# SCH_IoT_STANDALONE_2024-02-11.net
KiCad netlist of a schematic drawn in EasyEDA
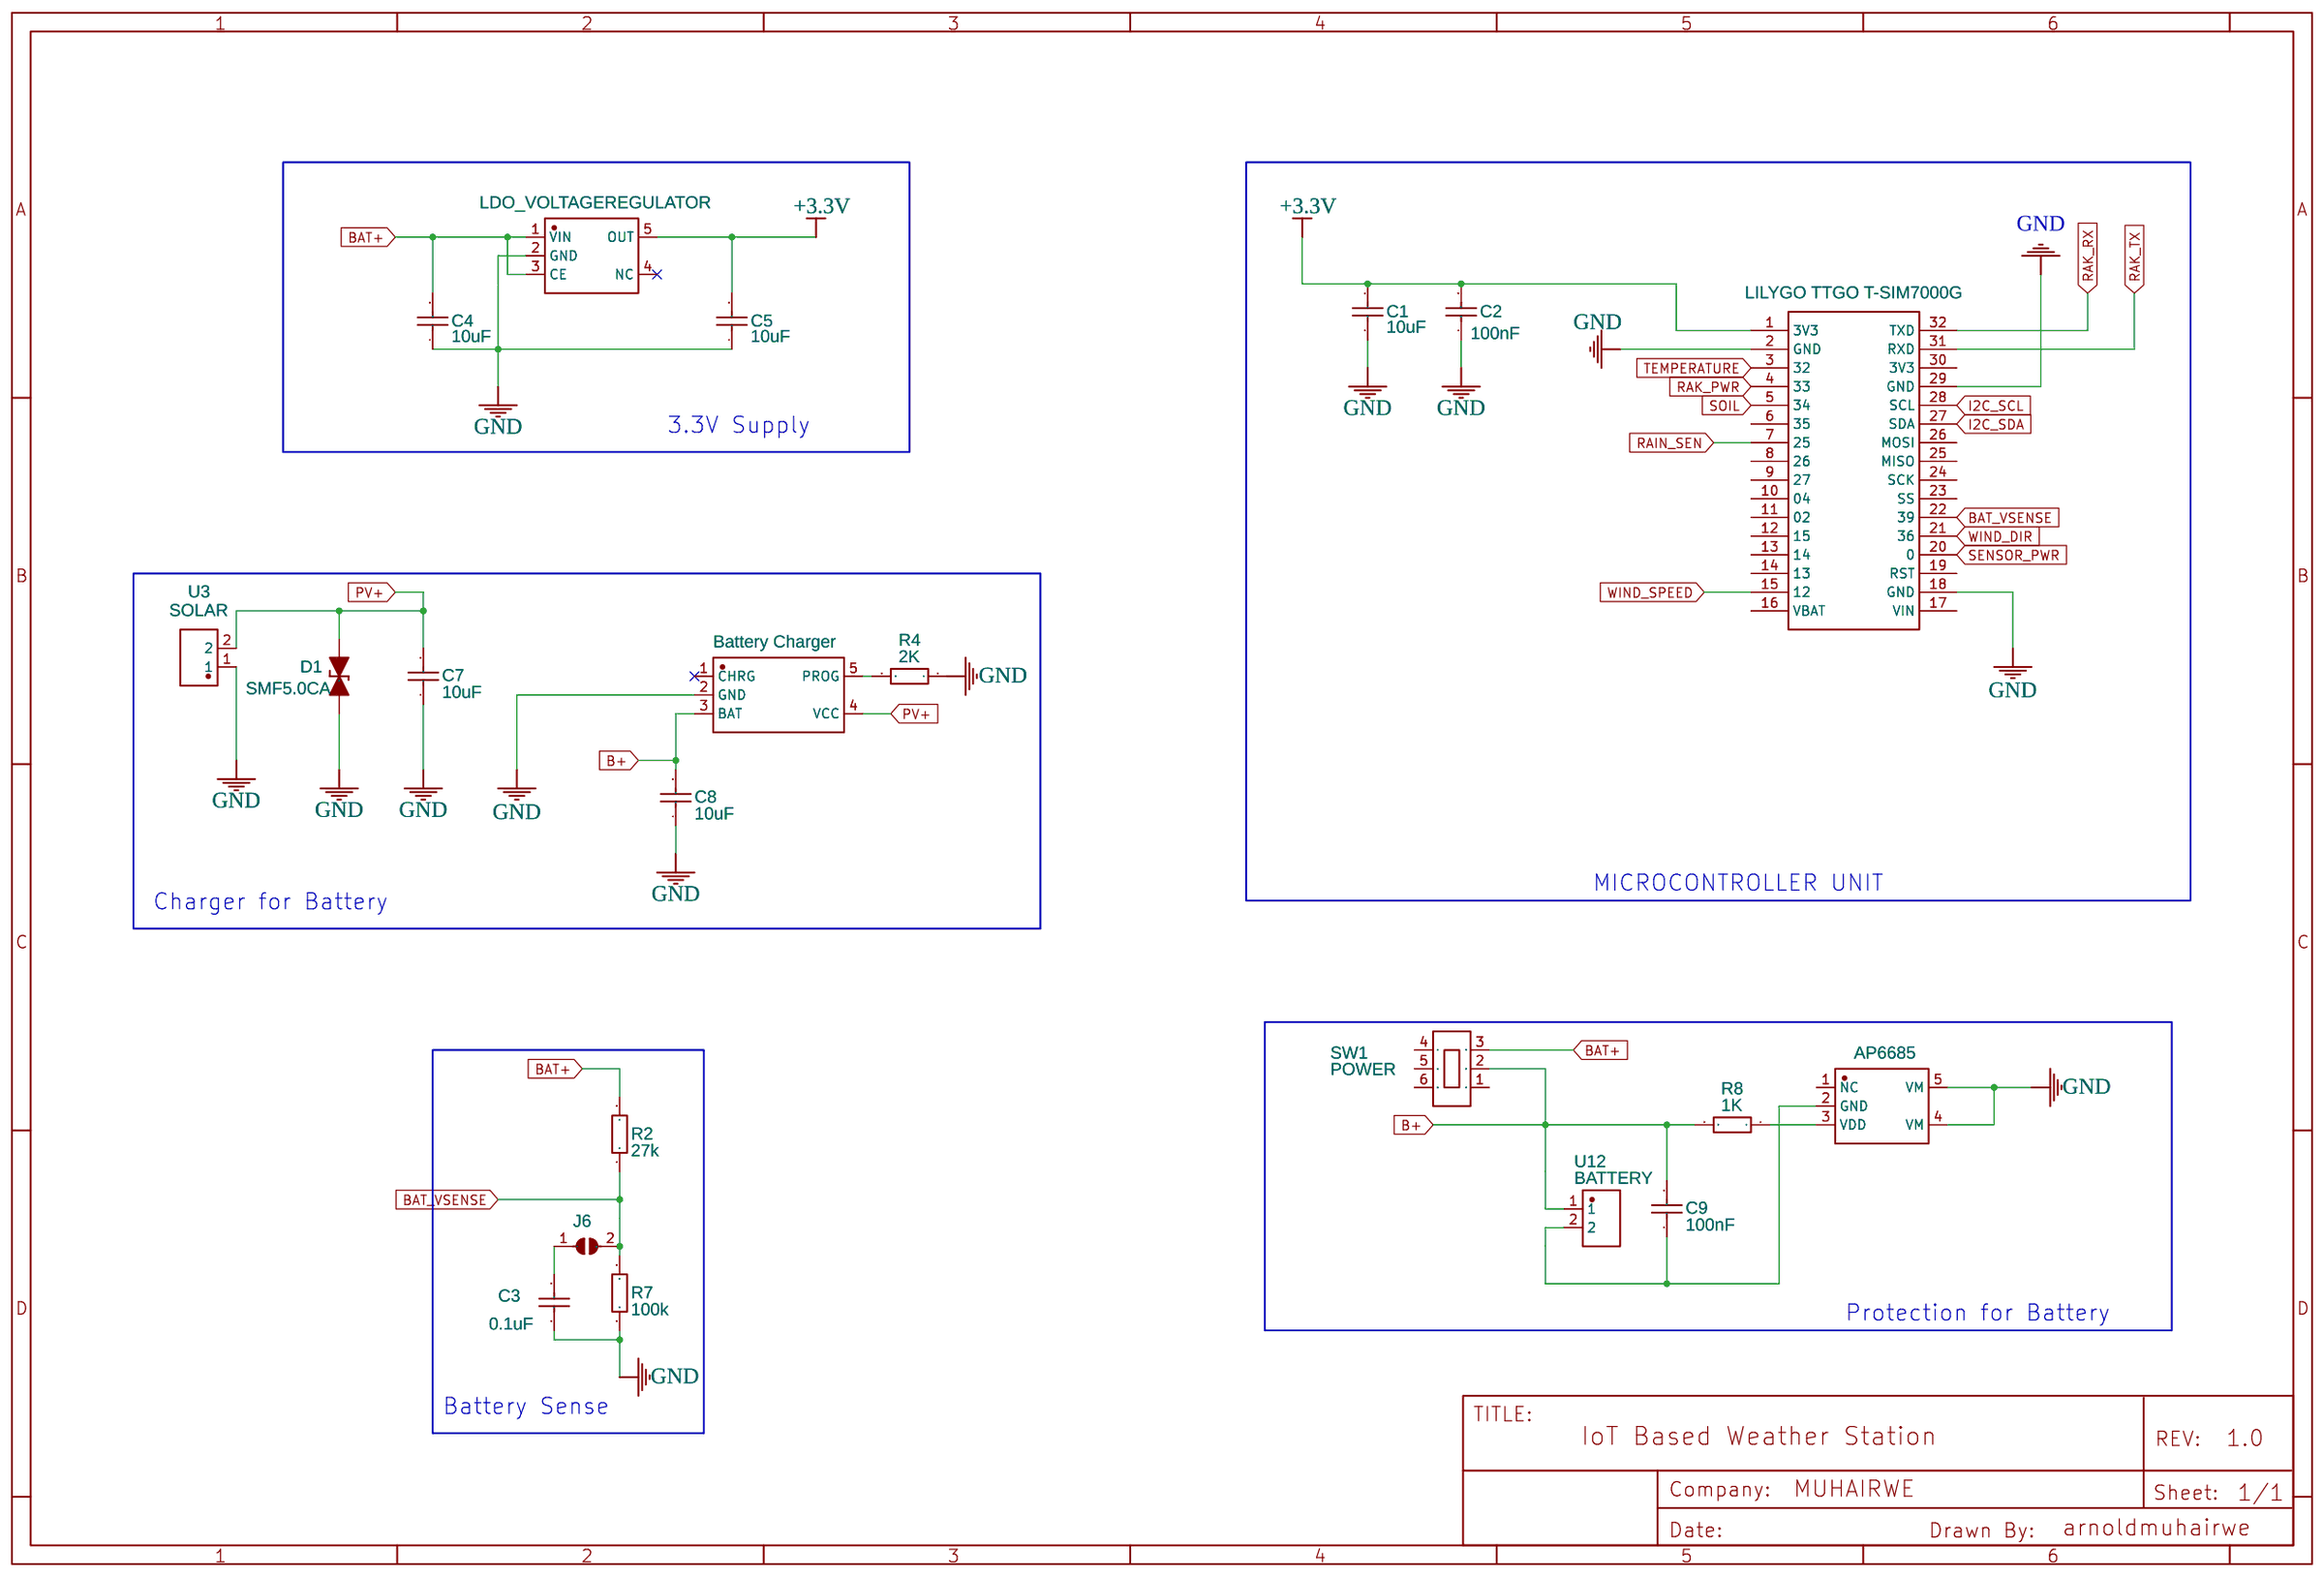
[diagram p0: LAYER1]
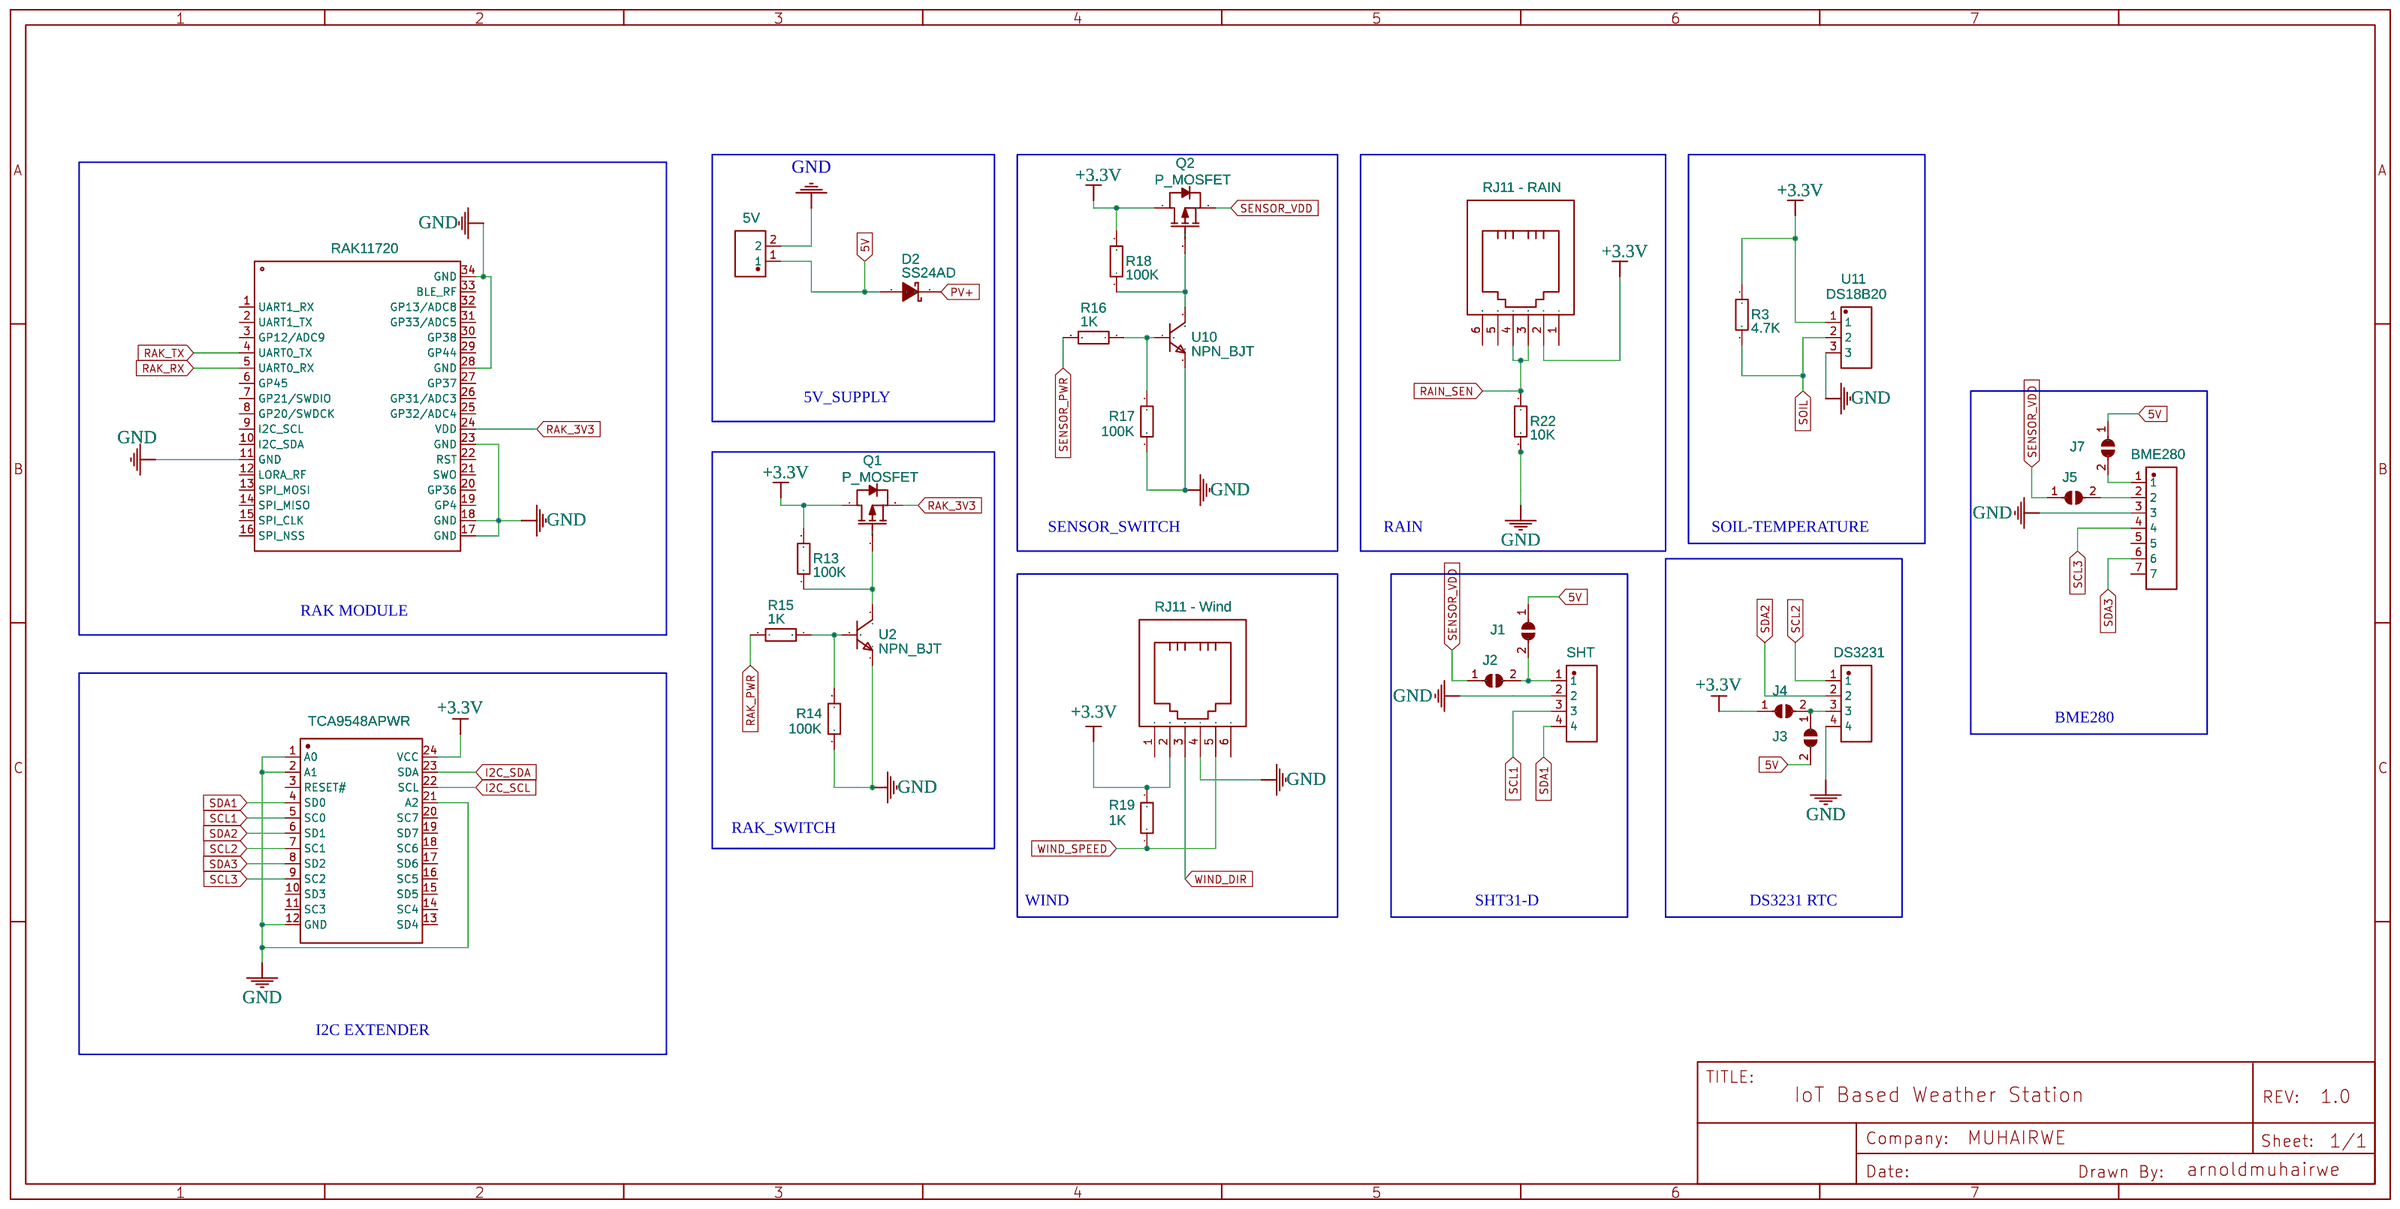
[diagram p1: LAYER2]

(export (version "E")
  (design (tool "Eeschema 10.0.6"))
  (components
    (comp (ref "C1")
      (value "10uF")
      (fields (field (name "Manufacturer Part") "CL05A106MQ5NUNC") (field (name "Manufacturer") "SAMSUNG"))
      (libsource (lib "") (part "CL05A106MQ5NUNC"))
    )
    (comp (ref "C2")
      (value "100nF")
      (fields (field (name "Manufacturer Part") "CL05B104KO5NNNC") (field (name "Manufacturer") "SAMSUNG"))
      (libsource (lib "") (part "CL05B104KO5NNNC"))
    )
    (comp (ref "C3")
      (value "0.1uF")
      (fields (field (name "Manufacturer Part") "CL05B104KO5NNNC") (field (name "Manufacturer") "SAMSUNG"))
      (libsource (lib "") (part "CL05B104KO5NNNC"))
    )
    (comp (ref "C4")
      (value "10uF")
      (fields (field (name "Manufacturer Part") "CL05A106MQ5NUNC") (field (name "Manufacturer") "SAMSUNG"))
      (libsource (lib "") (part "CL05A106MQ5NUNC"))
    )
    (comp (ref "C5")
      (value "10uF")
      (fields (field (name "Manufacturer Part") "CL05A106MQ5NUNC") (field (name "Manufacturer") "SAMSUNG"))
      (libsource (lib "") (part "CL05A106MQ5NUNC"))
    )
    (comp (ref "C7")
      (value "10uF")
      (fields (field (name "Manufacturer Part") "CL05B104KO5NNNC") (field (name "Manufacturer") "SAMSUNG"))
      (libsource (lib "") (part "CL05B104KO5NNNC"))
    )
    (comp (ref "C8")
      (value "10uF")
      (fields (field (name "Manufacturer Part") "CL05B104KO5NNNC") (field (name "Manufacturer") "SAMSUNG"))
      (libsource (lib "") (part "CL05B104KO5NNNC"))
    )
    (comp (ref "C9")
      (value "100nF")
      (fields (field (name "Manufacturer Part") "CL05B104KO5NNNC") (field (name "Manufacturer") "SAMSUNG"))
      (libsource (lib "") (part "CL05B104KO5NNNC"))
    )
    (comp (ref "D1")
      (value "SMF5.0CA")
      (fields (field (name "Manufacturer") "FMS(美丽微)"))
      (libsource (lib "") (part "SMF5.0CA"))
    )
    (comp (ref "J6") (value "PAD-JUMPER-2") (libsource (lib "") (part "PAD-JUMPER-2")))
    (comp (ref "R2")
      (value "27k")
      (fields (field (name "Manufacturer Part") "0402WGF2000TCE") (field (name "Manufacturer") "UniOhm"))
      (libsource (lib "") (part "0402WGF2000TCE_1"))
    )
    (comp (ref "R4")
      (value "2K")
      (fields (field (name "Manufacturer Part") "0402WGF2000TCE") (field (name "Manufacturer") "UniOhm"))
      (libsource (lib "") (part "0402WGF2000TCE"))
    )
    (comp (ref "R7")
      (value "100k")
      (fields (field (name "Manufacturer Part") "0402WGF2000TCE") (field (name "Manufacturer") "UniOhm"))
      (libsource (lib "") (part "0402WGF2000TCE_1"))
    )
    (comp (ref "R8")
      (value "1K")
      (fields (field (name "Manufacturer Part") "0402WGF2000TCE") (field (name "Manufacturer") "UniOhm"))
      (libsource (lib "") (part "0402WGF2000TCE"))
    )
    (comp (ref "SW1")
      (value "POWER")
      (fields (field (name "Manufacturer Part") "MK-22D14-G020") (field (name "Manufacturer") "G-Switch(品赞)"))
      (libsource (lib "") (part "MK-22D14-G020"))
    )
    (comp (ref "U1") (value "LILYGO TTGO T-SIM7000G") (libsource (lib "") (part "LILYGO TTGO T-SIM7000G")))
    (comp (ref "U3")
      (value "SOLAR")
      (fields
        (field (name "Manufacturer Part") "KF127R-5.0-2P")
        (field (name "Manufacturer") "Cixi Kefa Elec")
      )
      (libsource (lib "") (part "KF127R-5.0-2P_1"))
    )
    (comp (ref "U5")
      (value "Battery Charger")
      (fields
        (field (name "Manufacturer Part") "LP4060AB5F-435")
        (field (name "Manufacturer") "LOWPOWER(微源半导体)")
      )
      (libsource (lib "") (part "LP4060AB5F-435"))
    )
    (comp (ref "U7")
      (value "LDO_VOLTAGEREGULATOR")
      (fields
        (field (name "Manufacturer Part") "XC6220B331MR")
        (field (name "Manufacturer") "TECH PUBLIC(台舟)")
      )
      (libsource (lib "") (part "XC6220B331MR"))
    )
    (comp (ref "U8")
      (value "AP6685")
      (fields (field (name "Manufacturer") "ALLPOWER(铨力)"))
      (libsource (lib "") (part "AP6685"))
    )
    (comp (ref "U12")
      (value "BATTERY")
      (fields
        (field (name "Manufacturer Part") "KF127R-5.0-2P")
        (field (name "Manufacturer") "Cixi Kefa Elec")
      )
      (libsource (lib "") (part "KF127R-5.0-2P"))
    )
    (comp (ref "CN1")
      (value "BME280")
      (fields (field (name "Manufacturer Part") "1*7pin排间距2.54mm"))
      (libsource (lib "") (part "1*7PIN排间距2.54MM"))
    )
    (comp (ref "D2")
      (value "SS24AD")
      (fields (field (name "Manufacturer") "ST(先科)"))
      (libsource (lib "") (part "SS24AD"))
    )
    (comp (ref "J1") (value "PAD-JUMPER-2") (libsource (lib "") (part "PAD-JUMPER-2_1")))
    (comp (ref "J2") (value "PAD-JUMPER-2") (libsource (lib "") (part "PAD-JUMPER-2")))
    (comp (ref "J3") (value "PAD-JUMPER-2") (libsource (lib "") (part "PAD-JUMPER-2_1")))
    (comp (ref "J4") (value "PAD-JUMPER-2") (libsource (lib "") (part "PAD-JUMPER-2")))
    (comp (ref "J5") (value "PAD-JUMPER-2") (libsource (lib "") (part "PAD-JUMPER-2")))
    (comp (ref "J7") (value "PAD-JUMPER-2") (libsource (lib "") (part "PAD-JUMPER-2_1")))
    (comp (ref "P1")
      (value "SHT")
      (fields (field (name "Manufacturer Part") "HEADER_1*4P"))
      (libsource (lib "") (part "HEADER_1*4P"))
    )
    (comp (ref "P2")
      (value "DS3231")
      (fields (field (name "Manufacturer Part") "HEADER_1*4P"))
      (libsource (lib "") (part "HEADER_1*4P"))
    )
    (comp (ref "Q1")
      (value "P_MOSFET")
      (fields (field (name "Manufacturer Part") "SI2301S") (field (name "Manufacturer") "MDD"))
      (libsource (lib "") (part "SI2301S_C427389"))
    )
    (comp (ref "Q2")
      (value "P_MOSFET")
      (fields (field (name "Manufacturer Part") "SI2301S") (field (name "Manufacturer") "MDD"))
      (libsource (lib "") (part "SI2301S_C427389"))
    )
    (comp (ref "R3")
      (value "4.7K")
      (fields (field (name "Manufacturer Part") "0402WGF2000TCE") (field (name "Manufacturer") "UniOhm"))
      (libsource (lib "") (part "0402WGF2000TCE"))
    )
    (comp (ref "R13")
      (value "100K")
      (fields (field (name "Manufacturer Part") "0402WGF2000TCE") (field (name "Manufacturer") "UniOhm"))
      (libsource (lib "") (part "0402WGF2000TCE_2"))
    )
    (comp (ref "R14")
      (value "100K")
      (fields (field (name "Manufacturer Part") "0402WGF2000TCE") (field (name "Manufacturer") "UniOhm"))
      (libsource (lib "") (part "0402WGF2000TCE_2"))
    )
    (comp (ref "R15")
      (value "1K")
      (fields (field (name "Manufacturer Part") "0402WGF2000TCE") (field (name "Manufacturer") "UniOhm"))
      (libsource (lib "") (part "0402WGF2000TCE_1"))
    )
    (comp (ref "R16")
      (value "1K")
      (fields (field (name "Manufacturer Part") "0402WGF2000TCE") (field (name "Manufacturer") "UniOhm"))
      (libsource (lib "") (part "0402WGF2000TCE_1"))
    )
    (comp (ref "R17")
      (value "100K")
      (fields (field (name "Manufacturer Part") "0402WGF2000TCE") (field (name "Manufacturer") "UniOhm"))
      (libsource (lib "") (part "0402WGF2000TCE_2"))
    )
    (comp (ref "R18")
      (value "100K")
      (fields (field (name "Manufacturer Part") "0402WGF2000TCE") (field (name "Manufacturer") "UniOhm"))
      (libsource (lib "") (part "0402WGF2000TCE_2"))
    )
    (comp (ref "R19")
      (value "1K")
      (fields (field (name "Manufacturer Part") "0402WGF2000TCE") (field (name "Manufacturer") "UniOhm"))
      (libsource (lib "") (part "0402WGF2000TCE_2"))
    )
    (comp (ref "R22")
      (value "10K")
      (fields (field (name "Manufacturer Part") "0402WGF2000TCE") (field (name "Manufacturer") "UniOhm"))
      (libsource (lib "") (part "0402WGF2000TCE"))
    )
    (comp (ref "RAINFALL1")
      (value "RJ11 - RAIN")
      (fields (field (name "Manufacturer Part") "DS1133-S60BPX") (field (name "Manufacturer") "CONNFLY"))
      (libsource (lib "") (part "DS1133-S60BPX"))
    )
    (comp (ref "U2")
      (value "NPN_BJT")
      (fields (field (name "Manufacturer Part") "MMBT3904Q") (field (name "Manufacturer") "YANGJIE(扬杰)"))
      (libsource (lib "") (part "MMBT3904Q"))
    )
    (comp (ref "U4")
      (value "TCA9548APWR")
      (fields (field (name "Manufacturer") "TI(德州仪器)"))
      (libsource (lib "") (part "TCA9548APWR"))
    )
    (comp (ref "U9")
      (value "RAK11720")
      (fields (field (name "Manufacturer Part") "RAKwireless"))
      (libsource (lib "") (part "RAK11720"))
    )
    (comp (ref "U10")
      (value "NPN_BJT")
      (fields (field (name "Manufacturer Part") "MMBT3904Q") (field (name "Manufacturer") "YANGJIE(扬杰)"))
      (libsource (lib "") (part "MMBT3904Q"))
    )
    (comp (ref "U11") (value "DS18B20") (libsource (lib "") (part "HEADER - HEADER-FEMALE-2.54_1X3")))
    (comp (ref "U13")
      (value "5V")
      (fields
        (field (name "Manufacturer Part") "KF127R-5.0-2P")
        (field (name "Manufacturer") "Cixi Kefa Elec")
      )
      (libsource (lib "") (part "KF127R-5.0-2P"))
    )
    (comp (ref "WIND1")
      (value "RJ11 - Wind")
      (fields
        (field (name "Manufacturer Part") "FRJ11001-1100K6K20")
        (field (name "Manufacturer") "TXGA(特思嘉)")
      )
      (libsource (lib "") (part "FRJ11001-1100K6K20"))
    )
  )
  (nets
    (net (code "1") (name "+3.3V") (class "Default")
      (node (ref "C1") (pin "2") (pinfunction "2_2") (pintype "input"))
      (node (ref "C2") (pin "2") (pinfunction "2_2") (pintype "input"))
      (node (ref "C5") (pin "2") (pinfunction "2_2") (pintype "input"))
      (node (ref "J4") (pin "1") (pinfunction "A_1") (pintype "unspecified"))
      (node (ref "Q1") (pin "3") (pinfunction "D_3") (pintype "unspecified"))
      (node (ref "Q2") (pin "3") (pinfunction "D_3") (pintype "unspecified"))
      (node (ref "R13") (pin "2") (pinfunction "2_2") (pintype "input"))
      (node (ref "R18") (pin "2") (pinfunction "2_2") (pintype "input"))
      (node (ref "R19") (pin "2") (pinfunction "2_2") (pintype "input"))
      (node (ref "R3") (pin "1") (pinfunction "1_1") (pintype "input"))
      (node (ref "RAINFALL1") (pin "2") (pinfunction "2_2") (pintype "unspecified"))
      (node (ref "U1") (pin "1") (pinfunction "3V3_1") (pintype "unspecified"))
      (node (ref "U11") (pin "1") (pinfunction "1_1") (pintype "unspecified"))
      (node (ref "U4") (pin "24") (pinfunction "VCC_24") (pintype "unspecified"))
      (node (ref "U7") (pin "5") (pinfunction "OUT_5") (pintype "unspecified"))
      (node (ref "WIND1") (pin "2") (pinfunction "2_2") (pintype "unspecified"))
    )
    (net (code "2") (name "5V") (class "Default")
      (node (ref "D2") (pin "2") (pinfunction "A_2") (pintype "unspecified"))
      (node (ref "J1") (pin "1") (pinfunction "A_1") (pintype "unspecified"))
      (node (ref "J3") (pin "2") (pinfunction "B_2") (pintype "unspecified"))
      (node (ref "J7") (pin "1") (pinfunction "A_1") (pintype "unspecified"))
      (node (ref "U13") (pin "1") (pinfunction "1_1") (pintype "unspecified"))
    )
    (net (code "3") (name "B+") (class "Default")
      (node (ref "C8") (pin "2") (pinfunction "2_2") (pintype "input"))
      (node (ref "C9") (pin "2") (pinfunction "2_2") (pintype "input"))
      (node (ref "R8") (pin "2") (pinfunction "2_2") (pintype "input"))
      (node (ref "SW1") (pin "2") (pinfunction "2_2") (pintype "unspecified"))
      (node (ref "U12") (pin "1") (pinfunction "1_1") (pintype "unspecified"))
      (node (ref "U5") (pin "3") (pinfunction "BAT_3") (pintype "unspecified"))
    )
    (net (code "4") (name "BAT+") (class "Default")
      (node (ref "C4") (pin "2") (pinfunction "2_2") (pintype "input"))
      (node (ref "R2") (pin "2") (pinfunction "2_2") (pintype "input"))
      (node (ref "SW1") (pin "3") (pinfunction "3_3") (pintype "unspecified"))
      (node (ref "U7") (pin "1") (pinfunction "VIN_1") (pintype "unspecified"))
      (node (ref "U7") (pin "3") (pinfunction "CE_3") (pintype "unspecified"))
    )
    (net (code "5") (name "BAT_VSENSE") (class "Default")
      (node (ref "J6") (pin "2") (pinfunction "B_2") (pintype "unspecified"))
      (node (ref "R2") (pin "1") (pinfunction "1_1") (pintype "input"))
      (node (ref "R7") (pin "2") (pinfunction "2_2") (pintype "input"))
      (node (ref "U1") (pin "22") (pinfunction "39_22") (pintype "unspecified"))
    )
    (net (code "6") (name "GND") (class "Default")
      (node (ref "C1") (pin "1") (pinfunction "1_1") (pintype "input"))
      (node (ref "C2") (pin "1") (pinfunction "1_1") (pintype "input"))
      (node (ref "C3") (pin "1") (pinfunction "1_1") (pintype "input"))
      (node (ref "C4") (pin "1") (pinfunction "1_1") (pintype "input"))
      (node (ref "C5") (pin "1") (pinfunction "1_1") (pintype "input"))
      (node (ref "C7") (pin "1") (pinfunction "1_1") (pintype "input"))
      (node (ref "C8") (pin "1") (pinfunction "1_1") (pintype "input"))
      (node (ref "CN1") (pin "3") (pinfunction "3_3") (pintype "unspecified"))
      (node (ref "D1") (pin "1") (pinfunction "K_1") (pintype "unspecified"))
      (node (ref "P1") (pin "2") (pinfunction "2_2") (pintype "unspecified"))
      (node (ref "P2") (pin "4") (pinfunction "4_4") (pintype "unspecified"))
      (node (ref "R14") (pin "1") (pinfunction "1_1") (pintype "input"))
      (node (ref "R17") (pin "1") (pinfunction "1_1") (pintype "input"))
      (node (ref "R22") (pin "2") (pinfunction "2_2") (pintype "input"))
      (node (ref "R4") (pin "1") (pinfunction "1_1") (pintype "input"))
      (node (ref "R7") (pin "1") (pinfunction "1_1") (pintype "input"))
      (node (ref "U1") (pin "18") (pinfunction "GND_18") (pintype "unspecified"))
      (node (ref "U1") (pin "2") (pinfunction "GND_2") (pintype "unspecified"))
      (node (ref "U1") (pin "29") (pinfunction "GND_29") (pintype "unspecified"))
      (node (ref "U10") (pin "2") (pinfunction "E_2") (pintype "unspecified"))
      (node (ref "U11") (pin "3") (pinfunction "3_3") (pintype "unspecified"))
      (node (ref "U13") (pin "2") (pinfunction "2_2") (pintype "unspecified"))
      (node (ref "U2") (pin "2") (pinfunction "E_2") (pintype "unspecified"))
      (node (ref "U3") (pin "1") (pinfunction "1_1") (pintype "unspecified"))
      (node (ref "U4") (pin "1") (pinfunction "A0_1") (pintype "unspecified"))
      (node (ref "U4") (pin "12") (pinfunction "GND_12") (pintype "unspecified"))
      (node (ref "U4") (pin "2") (pinfunction "A1_2") (pintype "unspecified"))
      (node (ref "U4") (pin "21") (pinfunction "A2_21") (pintype "unspecified"))
      (node (ref "U5") (pin "2") (pinfunction "GND_2") (pintype "unspecified"))
      (node (ref "U7") (pin "2") (pinfunction "GND_2") (pintype "unspecified"))
      (node (ref "U8") (pin "4") (pinfunction "VM_4") (pintype "unspecified"))
      (node (ref "U8") (pin "5") (pinfunction "VM_5") (pintype "unspecified"))
      (node (ref "U9") (pin "11") (pinfunction "GND_11") (pintype "unspecified"))
      (node (ref "U9") (pin "17") (pinfunction "GND_17") (pintype "unspecified"))
      (node (ref "U9") (pin "18") (pinfunction "GND_18") (pintype "unspecified"))
      (node (ref "U9") (pin "23") (pinfunction "GND_23") (pintype "unspecified"))
      (node (ref "U9") (pin "28") (pinfunction "GND_28") (pintype "unspecified"))
      (node (ref "U9") (pin "34") (pinfunction "GND_34") (pintype "unspecified"))
      (node (ref "WIND1") (pin "4") (pinfunction "4_4") (pintype "unspecified"))
    )
    (net (code "7") (name "I2C_SCL") (class "Default")
      (node (ref "U1") (pin "28") (pinfunction "SCL_28") (pintype "unspecified"))
      (node (ref "U4") (pin "22") (pinfunction "SCL_22") (pintype "unspecified"))
    )
    (net (code "8") (name "I2C_SDA") (class "Default")
      (node (ref "U1") (pin "27") (pinfunction "SDA_27") (pintype "unspecified"))
      (node (ref "U4") (pin "23") (pinfunction "SDA_23") (pintype "unspecified"))
    )
    (net (code "9") (name "Net-(J1-B)") (class "Default")
      (node (ref "J1") (pin "2") (pinfunction "B_2") (pintype "unspecified"))
      (node (ref "J2") (pin "2") (pinfunction "B_2") (pintype "unspecified"))
      (node (ref "P1") (pin "1") (pinfunction "1_1") (pintype "unspecified"))
    )
    (net (code "10") (name "Net-(J3-A)") (class "Default")
      (node (ref "J3") (pin "1") (pinfunction "A_1") (pintype "unspecified"))
      (node (ref "J4") (pin "2") (pinfunction "B_2") (pintype "unspecified"))
      (node (ref "P2") (pin "3") (pinfunction "3_3") (pintype "unspecified"))
    )
    (net (code "11") (name "Net-(J5-B)") (class "Default")
      (node (ref "CN1") (pin "2") (pinfunction "2_2") (pintype "unspecified"))
      (node (ref "J5") (pin "2") (pinfunction "B_2") (pintype "unspecified"))
    )
    (net (code "12") (name "Net-(J6-A)") (class "Default")
      (node (ref "C3") (pin "2") (pinfunction "2_2") (pintype "input"))
      (node (ref "J6") (pin "1") (pinfunction "A_1") (pintype "unspecified"))
    )
    (net (code "13") (name "Net-(J7-B)") (class "Default")
      (node (ref "CN1") (pin "1") (pinfunction "1_1") (pintype "unspecified"))
      (node (ref "J7") (pin "2") (pinfunction "B_2") (pintype "unspecified"))
    )
    (net (code "14") (name "Net-(Q1-G)") (class "Default")
      (node (ref "Q1") (pin "1") (pinfunction "G_1") (pintype "unspecified"))
      (node (ref "R13") (pin "1") (pinfunction "1_1") (pintype "input"))
      (node (ref "U2") (pin "3") (pinfunction "C_3") (pintype "unspecified"))
    )
    (net (code "15") (name "Net-(Q2-G)") (class "Default")
      (node (ref "Q2") (pin "1") (pinfunction "G_1") (pintype "unspecified"))
      (node (ref "R18") (pin "1") (pinfunction "1_1") (pintype "input"))
      (node (ref "U10") (pin "3") (pinfunction "C_3") (pintype "unspecified"))
    )
    (net (code "16") (name "Net-(U2-B)") (class "Default")
      (node (ref "R14") (pin "2") (pinfunction "2_2") (pintype "input"))
      (node (ref "R15") (pin "1") (pinfunction "1_1") (pintype "input"))
      (node (ref "U2") (pin "1") (pinfunction "B_1") (pintype "unspecified"))
    )
    (net (code "17") (name "Net-(U5-PROG)") (class "Default")
      (node (ref "R4") (pin "2") (pinfunction "2_2") (pintype "input"))
      (node (ref "U5") (pin "5") (pinfunction "PROG_5") (pintype "unspecified"))
    )
    (net (code "18") (name "Net-(U8-GND)") (class "Default")
      (node (ref "C9") (pin "1") (pinfunction "1_1") (pintype "input"))
      (node (ref "U12") (pin "2") (pinfunction "2_2") (pintype "unspecified"))
      (node (ref "U8") (pin "2") (pinfunction "GND_2") (pintype "unspecified"))
    )
    (net (code "19") (name "Net-(U8-VDD)") (class "Default")
      (node (ref "R8") (pin "1") (pinfunction "1_1") (pintype "input"))
      (node (ref "U8") (pin "3") (pinfunction "VDD_3") (pintype "unspecified"))
    )
    (net (code "20") (name "Net-(U10-B)") (class "Default")
      (node (ref "R16") (pin "1") (pinfunction "1_1") (pintype "input"))
      (node (ref "R17") (pin "2") (pinfunction "2_2") (pintype "input"))
      (node (ref "U10") (pin "1") (pinfunction "B_1") (pintype "unspecified"))
    )
    (net (code "21") (name "PV+") (class "Default")
      (node (ref "C7") (pin "2") (pinfunction "2_2") (pintype "input"))
      (node (ref "D1") (pin "2") (pinfunction "A_2") (pintype "unspecified"))
      (node (ref "D2") (pin "1") (pinfunction "C_1") (pintype "unspecified"))
      (node (ref "U3") (pin "2") (pinfunction "2_2") (pintype "unspecified"))
      (node (ref "U5") (pin "4") (pinfunction "VCC_4") (pintype "unspecified"))
    )
    (net (code "22") (name "RAIN_SEN") (class "Default")
      (node (ref "R22") (pin "1") (pinfunction "1_1") (pintype "input"))
      (node (ref "RAINFALL1") (pin "3") (pinfunction "3_3") (pintype "unspecified"))
      (node (ref "RAINFALL1") (pin "4") (pinfunction "4_4") (pintype "unspecified"))
      (node (ref "U1") (pin "7") (pinfunction "25_7") (pintype "unspecified"))
    )
    (net (code "23") (name "RAK_3V3") (class "Default")
      (node (ref "Q1") (pin "2") (pinfunction "S_2") (pintype "unspecified"))
      (node (ref "U9") (pin "24") (pinfunction "VDD_24") (pintype "unspecified"))
    )
    (net (code "24") (name "RAK_PWR") (class "Default")
      (node (ref "R15") (pin "2") (pinfunction "2_2") (pintype "input"))
      (node (ref "U1") (pin "4") (pinfunction "33_4") (pintype "unspecified"))
    )
    (net (code "25") (name "RAK_RX") (class "Default")
      (node (ref "U1") (pin "32") (pinfunction "TXD_32") (pintype "unspecified"))
      (node (ref "U9") (pin "5") (pinfunction "UART0_RX_5") (pintype "unspecified"))
    )
    (net (code "26") (name "RAK_TX") (class "Default")
      (node (ref "U1") (pin "31") (pinfunction "RXD_31") (pintype "unspecified"))
      (node (ref "U9") (pin "4") (pinfunction "UART0_TX_4") (pintype "unspecified"))
    )
    (net (code "27") (name "SCL1") (class "Default")
      (node (ref "P1") (pin "3") (pinfunction "3_3") (pintype "unspecified"))
      (node (ref "U4") (pin "5") (pinfunction "SC0_5") (pintype "unspecified"))
    )
    (net (code "28") (name "SCL2") (class "Default")
      (node (ref "P2") (pin "1") (pinfunction "1_1") (pintype "unspecified"))
      (node (ref "U4") (pin "7") (pinfunction "SC1_7") (pintype "unspecified"))
    )
    (net (code "29") (name "SCL3") (class "Default")
      (node (ref "CN1") (pin "4") (pinfunction "4_4") (pintype "unspecified"))
      (node (ref "U4") (pin "9") (pinfunction "SC2_9") (pintype "unspecified"))
    )
    (net (code "30") (name "SDA1") (class "Default")
      (node (ref "P1") (pin "4") (pinfunction "4_4") (pintype "unspecified"))
      (node (ref "U4") (pin "4") (pinfunction "SD0_4") (pintype "unspecified"))
    )
    (net (code "31") (name "SDA2") (class "Default")
      (node (ref "P2") (pin "2") (pinfunction "2_2") (pintype "unspecified"))
      (node (ref "U4") (pin "6") (pinfunction "SD1_6") (pintype "unspecified"))
    )
    (net (code "32") (name "SDA3") (class "Default")
      (node (ref "CN1") (pin "6") (pinfunction "6_6") (pintype "unspecified"))
      (node (ref "U4") (pin "8") (pinfunction "SD2_8") (pintype "unspecified"))
    )
    (net (code "33") (name "SENSOR_PWR") (class "Default")
      (node (ref "R16") (pin "2") (pinfunction "2_2") (pintype "input"))
      (node (ref "U1") (pin "20") (pinfunction "0_20") (pintype "unspecified"))
    )
    (net (code "34") (name "SENSOR_VDD") (class "Default")
      (node (ref "J2") (pin "1") (pinfunction "A_1") (pintype "unspecified"))
      (node (ref "J5") (pin "1") (pinfunction "A_1") (pintype "unspecified"))
      (node (ref "Q2") (pin "2") (pinfunction "S_2") (pintype "unspecified"))
    )
    (net (code "35") (name "SOIL") (class "Default")
      (node (ref "R3") (pin "2") (pinfunction "2_2") (pintype "input"))
      (node (ref "U1") (pin "5") (pinfunction "34_5") (pintype "unspecified"))
      (node (ref "U11") (pin "2") (pinfunction "2_2") (pintype "unspecified"))
    )
    (net (code "36") (name "TEMPERATURE") (class "Default")
      (node (ref "U1") (pin "3") (pinfunction "32_3") (pintype "unspecified"))
    )
    (net (code "37") (name "WIND_DIR") (class "Default")
      (node (ref "U1") (pin "21") (pinfunction "36_21") (pintype "unspecified"))
      (node (ref "WIND1") (pin "3") (pinfunction "3_3") (pintype "unspecified"))
    )
    (net (code "38") (name "WIND_SPEED") (class "Default")
      (node (ref "R19") (pin "1") (pinfunction "1_1") (pintype "input"))
      (node (ref "U1") (pin "15") (pinfunction "12_15") (pintype "unspecified"))
      (node (ref "WIND1") (pin "5") (pinfunction "5_5") (pintype "unspecified"))
    )
    (net (code "39") (name "unconnected-(CN1-Pad5)") (class "Default")
      (node (ref "CN1") (pin "5") (pinfunction "5_5") (pintype "unspecified"))
    )
    (net (code "40") (name "unconnected-(CN1-Pad7)") (class "Default")
      (node (ref "CN1") (pin "7") (pinfunction "7_7") (pintype "unspecified"))
    )
    (net (code "41") (name "unconnected-(RAINFALL1-Pad1)") (class "Default")
      (node (ref "RAINFALL1") (pin "1") (pinfunction "1_1") (pintype "unspecified"))
    )
    (net (code "42") (name "unconnected-(RAINFALL1-Pad5)") (class "Default")
      (node (ref "RAINFALL1") (pin "5") (pinfunction "5_5") (pintype "unspecified"))
    )
    (net (code "43") (name "unconnected-(RAINFALL1-Pad6)") (class "Default")
      (node (ref "RAINFALL1") (pin "6") (pinfunction "6_6") (pintype "unspecified"))
    )
    (net (code "44") (name "unconnected-(SW1-Pad1)") (class "Default")
      (node (ref "SW1") (pin "1") (pinfunction "1_1") (pintype "unspecified"))
    )
    (net (code "45") (name "unconnected-(SW1-Pad4)") (class "Default")
      (node (ref "SW1") (pin "4") (pinfunction "4_4") (pintype "unspecified"))
    )
    (net (code "46") (name "unconnected-(SW1-Pad5)") (class "Default")
      (node (ref "SW1") (pin "5") (pinfunction "5_5") (pintype "unspecified"))
    )
    (net (code "47") (name "unconnected-(SW1-Pad6)") (class "Default")
      (node (ref "SW1") (pin "6") (pinfunction "6_6") (pintype "unspecified"))
    )
    (net (code "48") (name "unconnected-(U1-02-Pad11)") (class "Default")
      (node (ref "U1") (pin "11") (pinfunction "02_11") (pintype "unspecified"))
    )
    (net (code "49") (name "unconnected-(U1-3V3-Pad30)") (class "Default")
      (node (ref "U1") (pin "30") (pinfunction "3V3_30") (pintype "unspecified"))
    )
    (net (code "50") (name "unconnected-(U1-04-Pad10)") (class "Default")
      (node (ref "U1") (pin "10") (pinfunction "04_10") (pintype "unspecified"))
    )
    (net (code "51") (name "unconnected-(U1-13-Pad14)") (class "Default")
      (node (ref "U1") (pin "14") (pinfunction "13_14") (pintype "unspecified"))
    )
    (net (code "52") (name "unconnected-(U1-14-Pad13)") (class "Default")
      (node (ref "U1") (pin "13") (pinfunction "14_13") (pintype "unspecified"))
    )
    (net (code "53") (name "unconnected-(U1-15-Pad12)") (class "Default")
      (node (ref "U1") (pin "12") (pinfunction "15_12") (pintype "unspecified"))
    )
    (net (code "54") (name "unconnected-(U1-26-Pad8)") (class "Default")
      (node (ref "U1") (pin "8") (pinfunction "26_8") (pintype "unspecified"))
    )
    (net (code "55") (name "unconnected-(U1-27-Pad9)") (class "Default")
      (node (ref "U1") (pin "9") (pinfunction "27_9") (pintype "unspecified"))
    )
    (net (code "56") (name "unconnected-(U1-35-Pad6)") (class "Default")
      (node (ref "U1") (pin "6") (pinfunction "35_6") (pintype "unspecified"))
    )
    (net (code "57") (name "unconnected-(U1-MISO-Pad25)") (class "Default")
      (node (ref "U1") (pin "25") (pinfunction "MISO_25") (pintype "unspecified"))
    )
    (net (code "58") (name "unconnected-(U1-MOSI-Pad26)") (class "Default")
      (node (ref "U1") (pin "26") (pinfunction "MOSI_26") (pintype "unspecified"))
    )
    (net (code "59") (name "unconnected-(U1-RST-Pad19)") (class "Default")
      (node (ref "U1") (pin "19") (pinfunction "RST_19") (pintype "unspecified"))
    )
    (net (code "60") (name "unconnected-(U1-SCK-Pad24)") (class "Default")
      (node (ref "U1") (pin "24") (pinfunction "SCK_24") (pintype "unspecified"))
    )
    (net (code "61") (name "unconnected-(U1-SS-Pad23)") (class "Default")
      (node (ref "U1") (pin "23") (pinfunction "SS_23") (pintype "unspecified"))
    )
    (net (code "62") (name "unconnected-(U1-VBAT-Pad16)") (class "Default")
      (node (ref "U1") (pin "16") (pinfunction "VBAT_16") (pintype "unspecified"))
    )
    (net (code "63") (name "unconnected-(U1-VIN-Pad17)") (class "Default")
      (node (ref "U1") (pin "17") (pinfunction "VIN_17") (pintype "unspecified"))
    )
    (net (code "64") (name "unconnected-(U4-RESET#-Pad3)") (class "Default")
      (node (ref "U4") (pin "3") (pinfunction "RESET#_3") (pintype "unspecified"))
    )
    (net (code "65") (name "unconnected-(U4-SC3-Pad11)") (class "Default")
      (node (ref "U4") (pin "11") (pinfunction "SC3_11") (pintype "unspecified"))
    )
    (net (code "66") (name "unconnected-(U4-SC4-Pad14)") (class "Default")
      (node (ref "U4") (pin "14") (pinfunction "SC4_14") (pintype "unspecified"))
    )
    (net (code "67") (name "unconnected-(U4-SC5-Pad16)") (class "Default")
      (node (ref "U4") (pin "16") (pinfunction "SC5_16") (pintype "unspecified"))
    )
    (net (code "68") (name "unconnected-(U4-SC6-Pad18)") (class "Default")
      (node (ref "U4") (pin "18") (pinfunction "SC6_18") (pintype "unspecified"))
    )
    (net (code "69") (name "unconnected-(U4-SC7-Pad20)") (class "Default")
      (node (ref "U4") (pin "20") (pinfunction "SC7_20") (pintype "unspecified"))
    )
    (net (code "70") (name "unconnected-(U4-SD3-Pad10)") (class "Default")
      (node (ref "U4") (pin "10") (pinfunction "SD3_10") (pintype "unspecified"))
    )
    (net (code "71") (name "unconnected-(U4-SD4-Pad13)") (class "Default")
      (node (ref "U4") (pin "13") (pinfunction "SD4_13") (pintype "unspecified"))
    )
    (net (code "72") (name "unconnected-(U4-SD5-Pad15)") (class "Default")
      (node (ref "U4") (pin "15") (pinfunction "SD5_15") (pintype "unspecified"))
    )
    (net (code "73") (name "unconnected-(U4-SD6-Pad17)") (class "Default")
      (node (ref "U4") (pin "17") (pinfunction "SD6_17") (pintype "unspecified"))
    )
    (net (code "74") (name "unconnected-(U4-SD7-Pad19)") (class "Default")
      (node (ref "U4") (pin "19") (pinfunction "SD7_19") (pintype "unspecified"))
    )
    (net (code "75") (name "unconnected-(U5-CHRG-Pad1)") (class "Default")
      (node (ref "U5") (pin "1") (pinfunction "CHRG_1") (pintype "unspecified+no_connect"))
    )
    (net (code "76") (name "unconnected-(U7-NC-Pad4)") (class "Default")
      (node (ref "U7") (pin "4") (pinfunction "NC_4") (pintype "unspecified+no_connect"))
    )
    (net (code "77") (name "unconnected-(U8-NC-Pad1)") (class "Default")
      (node (ref "U8") (pin "1") (pinfunction "NC_1") (pintype "unspecified"))
    )
    (net (code "78") (name "unconnected-(U9-BLE_RF-Pad33)") (class "Default")
      (node (ref "U9") (pin "33") (pinfunction "BLE_RF_33") (pintype "unspecified"))
    )
    (net (code "79") (name "unconnected-(U9-GP4-Pad19)") (class "Default")
      (node (ref "U9") (pin "19") (pinfunction "GP4_19") (pintype "unspecified"))
    )
    (net (code "80") (name "unconnected-(U9-GP12{slash}ADC9-Pad3)") (class "Default")
      (node (ref "U9") (pin "3") (pinfunction "GP12/ADC9_3") (pintype "unspecified"))
    )
    (net (code "81") (name "unconnected-(U9-GP13{slash}ADC8-Pad32)") (class "Default")
      (node (ref "U9") (pin "32") (pinfunction "GP13/ADC8_32") (pintype "unspecified"))
    )
    (net (code "82") (name "unconnected-(U9-GP20{slash}SWDCK-Pad8)") (class "Default")
      (node (ref "U9") (pin "8") (pinfunction "GP20/SWDCK_8") (pintype "unspecified"))
    )
    (net (code "83") (name "unconnected-(U9-GP21{slash}SWDIO-Pad7)") (class "Default")
      (node (ref "U9") (pin "7") (pinfunction "GP21/SWDIO_7") (pintype "unspecified"))
    )
    (net (code "84") (name "unconnected-(U9-GP31{slash}ADC3-Pad26)") (class "Default")
      (node (ref "U9") (pin "26") (pinfunction "GP31/ADC3_26") (pintype "unspecified"))
    )
    (net (code "85") (name "unconnected-(U9-GP32{slash}ADC4-Pad25)") (class "Default")
      (node (ref "U9") (pin "25") (pinfunction "GP32/ADC4_25") (pintype "unspecified"))
    )
    (net (code "86") (name "unconnected-(U9-GP33{slash}ADC5-Pad31)") (class "Default")
      (node (ref "U9") (pin "31") (pinfunction "GP33/ADC5_31") (pintype "unspecified"))
    )
    (net (code "87") (name "unconnected-(U9-GP36-Pad20)") (class "Default")
      (node (ref "U9") (pin "20") (pinfunction "GP36_20") (pintype "unspecified"))
    )
    (net (code "88") (name "unconnected-(U9-GP37-Pad27)") (class "Default")
      (node (ref "U9") (pin "27") (pinfunction "GP37_27") (pintype "unspecified"))
    )
    (net (code "89") (name "unconnected-(U9-GP38-Pad30)") (class "Default")
      (node (ref "U9") (pin "30") (pinfunction "GP38_30") (pintype "unspecified"))
    )
    (net (code "90") (name "unconnected-(U9-GP44-Pad29)") (class "Default")
      (node (ref "U9") (pin "29") (pinfunction "GP44_29") (pintype "unspecified"))
    )
    (net (code "91") (name "unconnected-(U9-GP45-Pad6)") (class "Default")
      (node (ref "U9") (pin "6") (pinfunction "GP45_6") (pintype "unspecified"))
    )
    (net (code "92") (name "unconnected-(U9-I2C_SCL-Pad9)") (class "Default")
      (node (ref "U9") (pin "9") (pinfunction "I2C_SCL_9") (pintype "unspecified"))
    )
    (net (code "93") (name "unconnected-(U9-I2C_SDA-Pad10)") (class "Default")
      (node (ref "U9") (pin "10") (pinfunction "I2C_SDA_10") (pintype "unspecified"))
    )
    (net (code "94") (name "unconnected-(U9-LORA_RF-Pad12)") (class "Default")
      (node (ref "U9") (pin "12") (pinfunction "LORA_RF_12") (pintype "unspecified"))
    )
    (net (code "95") (name "unconnected-(U9-RST-Pad22)") (class "Default")
      (node (ref "U9") (pin "22") (pinfunction "RST_22") (pintype "unspecified"))
    )
    (net (code "96") (name "unconnected-(U9-SPI_CLK-Pad15)") (class "Default")
      (node (ref "U9") (pin "15") (pinfunction "SPI_CLK_15") (pintype "unspecified"))
    )
    (net (code "97") (name "unconnected-(U9-SPI_MISO-Pad14)") (class "Default")
      (node (ref "U9") (pin "14") (pinfunction "SPI_MISO_14") (pintype "unspecified"))
    )
    (net (code "98") (name "unconnected-(U9-SPI_MOSI-Pad13)") (class "Default")
      (node (ref "U9") (pin "13") (pinfunction "SPI_MOSI_13") (pintype "unspecified"))
    )
    (net (code "99") (name "unconnected-(U9-SPI_NSS-Pad16)") (class "Default")
      (node (ref "U9") (pin "16") (pinfunction "SPI_NSS_16") (pintype "unspecified"))
    )
    (net (code "100") (name "unconnected-(U9-SWO-Pad21)") (class "Default")
      (node (ref "U9") (pin "21") (pinfunction "SWO_21") (pintype "unspecified"))
    )
    (net (code "101") (name "unconnected-(U9-UART1_RX-Pad1)") (class "Default")
      (node (ref "U9") (pin "1") (pinfunction "UART1_RX_1") (pintype "unspecified"))
    )
    (net (code "102") (name "unconnected-(U9-UART1_TX-Pad2)") (class "Default")
      (node (ref "U9") (pin "2") (pinfunction "UART1_TX_2") (pintype "unspecified"))
    )
    (net (code "103") (name "unconnected-(WIND1-Pad1)") (class "Default")
      (node (ref "WIND1") (pin "1") (pinfunction "1_1") (pintype "unspecified"))
    )
    (net (code "104") (name "unconnected-(WIND1-Pad6)") (class "Default")
      (node (ref "WIND1") (pin "6") (pinfunction "6_6") (pintype "unspecified"))
    )
  )
)
